# jetsonSerialBuffer.net
KiCad netlist of a schematic drawn in EAGLE
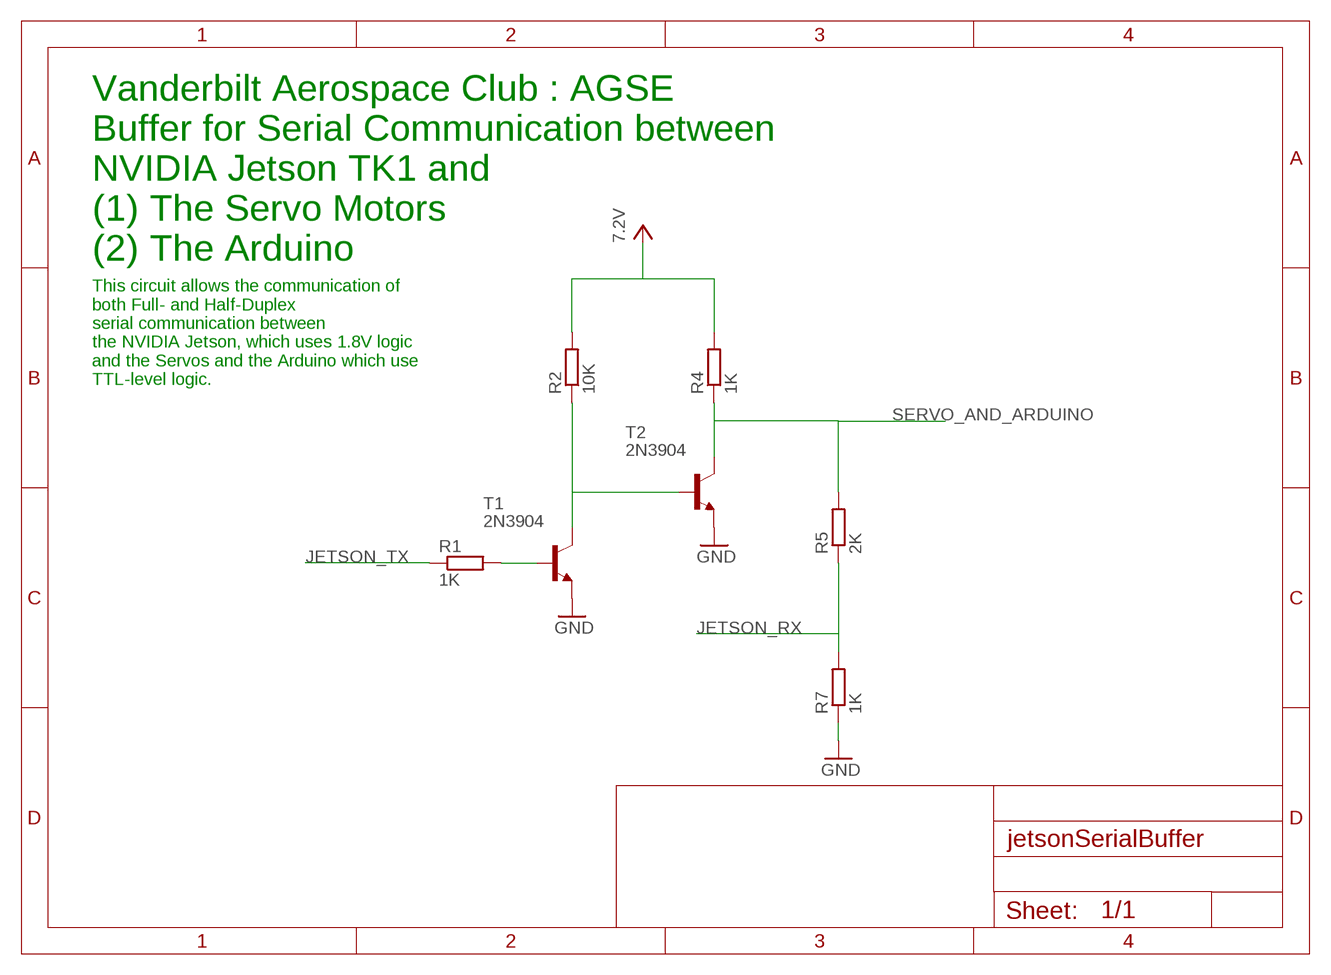
[diagram p0: schematic, sheet 1]

(export (version "E")
  (design (tool "Eeschema 10.0.6"))
  (components
    (comp (ref "R1")
      (value "1K")
      (footprint "eagle-import:0309_10")
      (libsource (lib "eagle-import") (part "R-EU_0309/10"))
    )
    (comp (ref "R2")
      (value "10K")
      (footprint "eagle-import:0309_10")
      (libsource (lib "eagle-import") (part "R-EU_0309/10"))
    )
    (comp (ref "R4")
      (value "1K")
      (footprint "eagle-import:0309_10")
      (libsource (lib "eagle-import") (part "R-EU_0309/10"))
    )
    (comp (ref "R5")
      (value "2K")
      (footprint "eagle-import:0309_10")
      (libsource (lib "eagle-import") (part "R-EU_0309/10"))
    )
    (comp (ref "R7")
      (value "1K")
      (footprint "eagle-import:0309_10")
      (libsource (lib "eagle-import") (part "R-EU_0309/10"))
    )
    (comp (ref "T1")
      (value "2N3904")
      (footprint "eagle-import:TO92")
      (libsource (lib "eagle-import") (part "2N3904"))
    )
    (comp (ref "T2")
      (value "2N3904")
      (footprint "eagle-import:TO92")
      (libsource (lib "eagle-import") (part "2N3904"))
    )
  )
  (nets
    (net (code "1") (name "/JETSON_RX") (class "Default")
      (node (ref "R5") (pin "1") (pinfunction "1_1") (pintype "passive"))
      (node (ref "R7") (pin "2") (pinfunction "2_2") (pintype "passive"))
    )
    (net (code "2") (name "/JETSON_TX") (class "Default")
      (node (ref "R1") (pin "1") (pinfunction "1_1") (pintype "passive"))
    )
    (net (code "3") (name "/SERVO_AND_ARDUINO") (class "Default")
      (node (ref "R4") (pin "1") (pinfunction "1_1") (pintype "passive"))
      (node (ref "R5") (pin "2") (pinfunction "2_2") (pintype "passive"))
      (node (ref "T2") (pin "1") (pinfunction "C_1") (pintype "passive"))
    )
    (net (code "4") (name "7.2V") (class "Default")
      (node (ref "R2") (pin "2") (pinfunction "2_2") (pintype "passive"))
      (node (ref "R4") (pin "2") (pinfunction "2_2") (pintype "passive"))
    )
    (net (code "5") (name "GND") (class "Default")
      (node (ref "R7") (pin "1") (pinfunction "1_1") (pintype "passive"))
      (node (ref "T1") (pin "3") (pinfunction "E_3") (pintype "passive"))
      (node (ref "T2") (pin "3") (pinfunction "E_3") (pintype "passive"))
    )
    (net (code "6") (name "Net-(T1-B)") (class "Default")
      (node (ref "R1") (pin "2") (pinfunction "2_2") (pintype "passive"))
      (node (ref "T1") (pin "2") (pinfunction "B_2") (pintype "passive"))
    )
    (net (code "7") (name "Net-(T1-C)") (class "Default")
      (node (ref "R2") (pin "1") (pinfunction "1_1") (pintype "passive"))
      (node (ref "T1") (pin "1") (pinfunction "C_1") (pintype "passive"))
      (node (ref "T2") (pin "2") (pinfunction "B_2") (pintype "passive"))
    )
  )
)
